# fingertip_20line_2.net
KiCad netlist of a schematic drawn in EAGLE
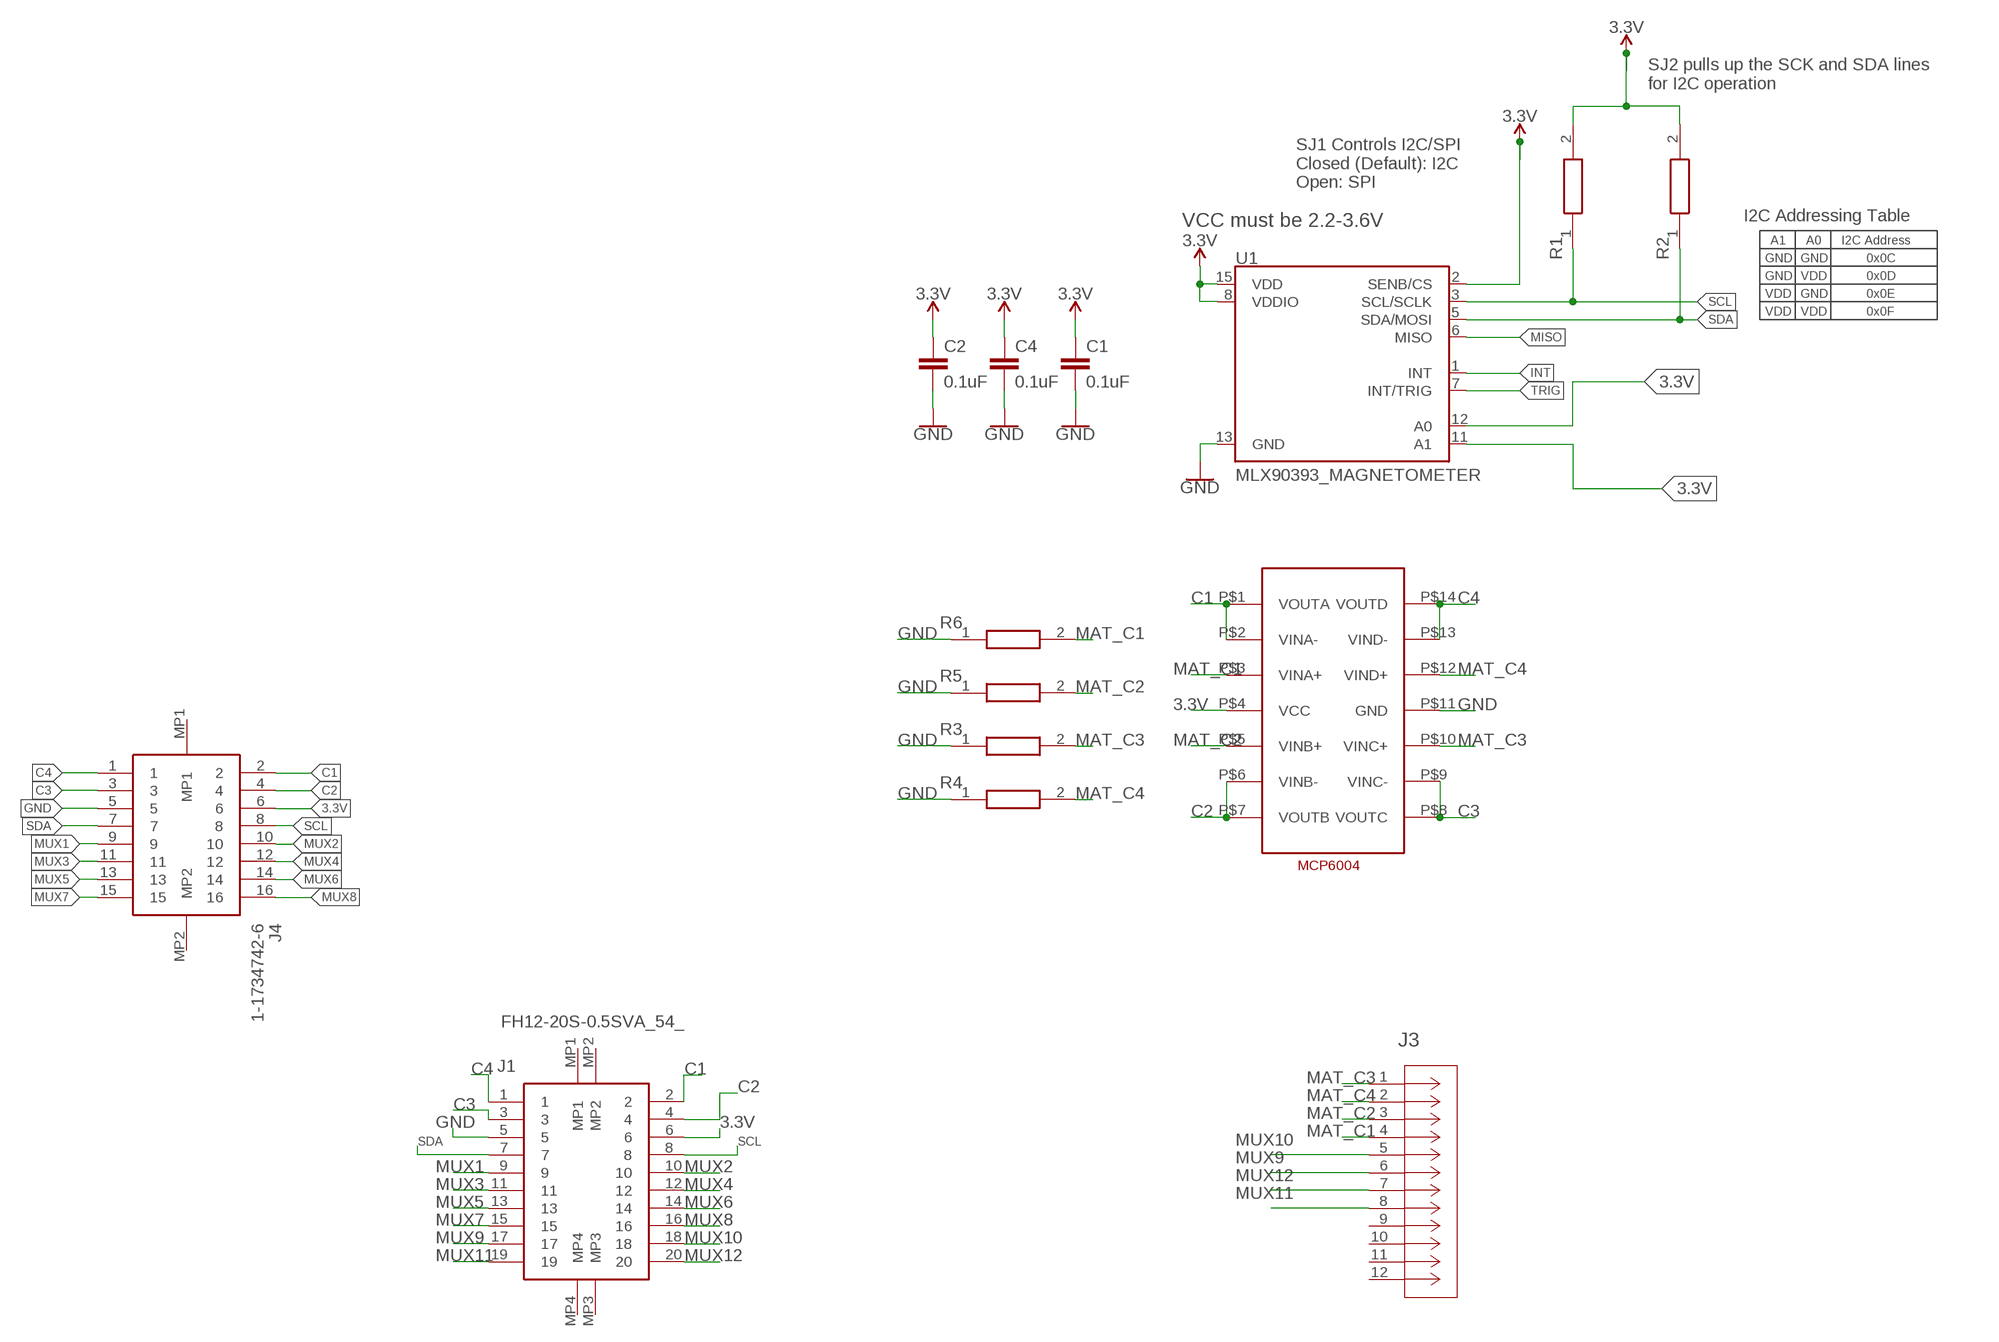
[diagram p0: schematic, sheet 1]

(export (version "E")
  (design (tool "Eeschema 10.0.6"))
  (components
    (comp (ref "C1")
      (value "0.1uF")
      (footprint "eagle-import:0603")
      (libsource (lib "eagle-import") (part "0.1UF-0603-25V-(+80/-20%)"))
    )
    (comp (ref "C2")
      (value "0.1uF")
      (footprint "eagle-import:0603")
      (libsource (lib "eagle-import") (part "0.1UF-0603-25V-(+80/-20%)"))
    )
    (comp (ref "C4")
      (value "0.1uF")
      (footprint "eagle-import:0603")
      (libsource (lib "eagle-import") (part "0.1UF-0603-25V-(+80/-20%)"))
    )
    (comp (ref "J1")
      (value "FH12-20S-0.5SVA_54_")
      (footprint "eagle-import:FH1220S05SVA54")
      (fields
        (field (name "MANUFACTURER_PART_NUMBER") "FH12-20S-0.5SVA(54)")
        (field (name "RS_PART_NUMBER") "1760102P")
      )
      (libsource (lib "eagle-import") (part "FH12-20S-0.5SVA_54_"))
    )
    (comp (ref "J3")
      (value "FH12-8S-1SV(55)")
      (footprint "eagle-import:CON8_1X8_DUTB1_HRS_HIR")
      (fields (field (name "COPYRIGHT") "Copyright (C) 2018 Accelerated Designs. All rights reserved"))
      (libsource (lib "eagle-import") (part "FH12-8S-1SV(55)"))
    )
    (comp (ref "J4")
      (value "1-1734742-6")
      (footprint "eagle-import:117347426")
      (fields (field (name "MOUSER_PART_NUMBER") "571-1-1734742-6"))
      (libsource (lib "eagle-import") (part "1-1734742-6"))
    )
    (comp (ref "R1")
      (value "ERJ-S02J103X")
      (footprint "eagle-import:RESC1005X40N")
      (libsource (lib "eagle-import") (part "ERJ-S02J103X"))
    )
    (comp (ref "R2")
      (value "ERJ-S02J103X")
      (footprint "eagle-import:RESC1005X40N")
      (libsource (lib "eagle-import") (part "ERJ-S02J103X"))
    )
    (comp (ref "R3")
      (value "ERJ-S02J103X")
      (footprint "eagle-import:RESC1005X40N")
      (libsource (lib "eagle-import") (part "ERJ-S02J103X"))
    )
    (comp (ref "R4")
      (value "ERJ-S02J103X")
      (footprint "eagle-import:RESC1005X40N")
      (libsource (lib "eagle-import") (part "ERJ-S02J103X"))
    )
    (comp (ref "R5")
      (value "ERJ-S02J103X")
      (footprint "eagle-import:RESC1005X40N")
      (libsource (lib "eagle-import") (part "ERJ-S02J103X"))
    )
    (comp (ref "R6")
      (value "ERJ-S02J103X")
      (footprint "eagle-import:RESC1005X40N")
      (libsource (lib "eagle-import") (part "ERJ-S02J103X"))
    )
    (comp (ref "U$2")
      (value "DECADE-MCP6004")
      (footprint "eagle-import:DECADE-MCP6003")
      (libsource (lib "eagle-import") (part "DECADE-MCP6004"))
    )
    (comp (ref "U1")
      (value "MLX90393_MAGNETOMETER")
      (footprint "eagle-import:QFN-16_WITH_AXIES")
      (libsource (lib "eagle-import") (part "MLX90393_MAGNETOMETER"))
    )
  )
  (nets
    (net (code "1") (name "/MAT_C1") (class "Default")
      (node (ref "J3") (pin "4") (pinfunction "4_4") (pintype "passive"))
      (node (ref "R6") (pin "2") (pinfunction "2_2") (pintype "bidirectional"))
      (node (ref "U$2") (pin "P$3") (pinfunction "VINA+_P$3") (pintype "bidirectional"))
    )
    (net (code "2") (name "/MAT_C2") (class "Default")
      (node (ref "J3") (pin "3") (pinfunction "3_3") (pintype "passive"))
      (node (ref "R5") (pin "2") (pinfunction "2_2") (pintype "bidirectional"))
      (node (ref "U$2") (pin "P$5") (pinfunction "VINB+_P$5") (pintype "bidirectional"))
    )
    (net (code "3") (name "/MAT_C3") (class "Default")
      (node (ref "J3") (pin "1") (pinfunction "1_1") (pintype "passive"))
      (node (ref "R3") (pin "2") (pinfunction "2_2") (pintype "bidirectional"))
      (node (ref "U$2") (pin "P$10") (pinfunction "VINC+_P$10") (pintype "bidirectional"))
    )
    (net (code "4") (name "/MAT_C4") (class "Default")
      (node (ref "J3") (pin "2") (pinfunction "2_2") (pintype "passive"))
      (node (ref "R4") (pin "2") (pinfunction "2_2") (pintype "bidirectional"))
      (node (ref "U$2") (pin "P$12") (pinfunction "VIND+_P$12") (pintype "bidirectional"))
    )
    (net (code "5") (name "/MUX9") (class "Default")
      (node (ref "J1") (pin "17") (pinfunction "17_17") (pintype "bidirectional"))
      (node (ref "J3") (pin "6") (pinfunction "6_6") (pintype "passive"))
    )
    (net (code "6") (name "/MUX10") (class "Default")
      (node (ref "J1") (pin "18") (pinfunction "18_18") (pintype "bidirectional"))
      (node (ref "J3") (pin "5") (pinfunction "5_5") (pintype "passive"))
    )
    (net (code "7") (name "/MUX11") (class "Default")
      (node (ref "J1") (pin "19") (pinfunction "19_19") (pintype "bidirectional"))
      (node (ref "J3") (pin "8") (pinfunction "8_8") (pintype "passive"))
    )
    (net (code "8") (name "/MUX12") (class "Default")
      (node (ref "J1") (pin "20") (pinfunction "20_20") (pintype "bidirectional"))
      (node (ref "J3") (pin "7") (pinfunction "7_7") (pintype "passive"))
    )
    (net (code "9") (name "3.3V") (class "Default")
      (node (ref "C1") (pin "1") (pinfunction "1_1") (pintype "passive"))
      (node (ref "C2") (pin "1") (pinfunction "1_1") (pintype "passive"))
      (node (ref "C4") (pin "1") (pinfunction "1_1") (pintype "passive"))
      (node (ref "J1") (pin "6") (pinfunction "6_6") (pintype "bidirectional"))
      (node (ref "J4") (pin "6") (pinfunction "6_6") (pintype "bidirectional"))
      (node (ref "R1") (pin "2") (pinfunction "2_2") (pintype "bidirectional"))
      (node (ref "R2") (pin "2") (pinfunction "2_2") (pintype "bidirectional"))
      (node (ref "U$2") (pin "P$4") (pinfunction "VCC_P$4") (pintype "bidirectional"))
      (node (ref "U1") (pin "11") (pinfunction "A1_11") (pintype "bidirectional"))
      (node (ref "U1") (pin "12") (pinfunction "A0_12") (pintype "bidirectional"))
      (node (ref "U1") (pin "15") (pinfunction "VDD_15") (pintype "bidirectional"))
      (node (ref "U1") (pin "2") (pinfunction "SENB/CS_2") (pintype "bidirectional"))
      (node (ref "U1") (pin "8") (pinfunction "VDDIO_8") (pintype "bidirectional"))
    )
    (net (code "10") (name "C1") (class "Default")
      (node (ref "J1") (pin "2") (pinfunction "2_2") (pintype "bidirectional"))
      (node (ref "J4") (pin "2") (pinfunction "2_2") (pintype "bidirectional"))
      (node (ref "U$2") (pin "P$1") (pinfunction "VOUTA_P$1") (pintype "bidirectional"))
      (node (ref "U$2") (pin "P$2") (pinfunction "VINA-_P$2") (pintype "bidirectional"))
    )
    (net (code "11") (name "C2") (class "Default")
      (node (ref "J1") (pin "4") (pinfunction "4_4") (pintype "bidirectional"))
      (node (ref "J4") (pin "4") (pinfunction "4_4") (pintype "bidirectional"))
      (node (ref "U$2") (pin "P$6") (pinfunction "VINB-_P$6") (pintype "bidirectional"))
      (node (ref "U$2") (pin "P$7") (pinfunction "VOUTB_P$7") (pintype "bidirectional"))
    )
    (net (code "12") (name "C3") (class "Default")
      (node (ref "J1") (pin "3") (pinfunction "3_3") (pintype "bidirectional"))
      (node (ref "J4") (pin "3") (pinfunction "3_3") (pintype "bidirectional"))
      (node (ref "U$2") (pin "P$8") (pinfunction "VOUTC_P$8") (pintype "bidirectional"))
      (node (ref "U$2") (pin "P$9") (pinfunction "VINC-_P$9") (pintype "bidirectional"))
    )
    (net (code "13") (name "C4") (class "Default")
      (node (ref "J1") (pin "1") (pinfunction "1_1") (pintype "bidirectional"))
      (node (ref "J4") (pin "1") (pinfunction "1_1") (pintype "bidirectional"))
      (node (ref "U$2") (pin "P$13") (pinfunction "VIND-_P$13") (pintype "bidirectional"))
      (node (ref "U$2") (pin "P$14") (pinfunction "VOUTD_P$14") (pintype "bidirectional"))
    )
    (net (code "14") (name "GND") (class "Default")
      (node (ref "C1") (pin "2") (pinfunction "2_2") (pintype "passive"))
      (node (ref "C2") (pin "2") (pinfunction "2_2") (pintype "passive"))
      (node (ref "C4") (pin "2") (pinfunction "2_2") (pintype "passive"))
      (node (ref "J1") (pin "5") (pinfunction "5_5") (pintype "bidirectional"))
      (node (ref "J4") (pin "5") (pinfunction "5_5") (pintype "bidirectional"))
      (node (ref "R3") (pin "1") (pinfunction "1_1") (pintype "bidirectional"))
      (node (ref "R4") (pin "1") (pinfunction "1_1") (pintype "bidirectional"))
      (node (ref "R5") (pin "1") (pinfunction "1_1") (pintype "bidirectional"))
      (node (ref "R6") (pin "1") (pinfunction "1_1") (pintype "bidirectional"))
      (node (ref "U$2") (pin "P$11") (pinfunction "GND_P$11") (pintype "bidirectional"))
      (node (ref "U1") (pin "13") (pinfunction "GND_13") (pintype "bidirectional"))
    )
    (net (code "15") (name "INT") (class "Default")
      (node (ref "U1") (pin "1") (pinfunction "INT_1") (pintype "bidirectional"))
    )
    (net (code "16") (name "MISO") (class "Default")
      (node (ref "U1") (pin "6") (pinfunction "MISO_6") (pintype "bidirectional"))
    )
    (net (code "17") (name "MUX1") (class "Default")
      (node (ref "J1") (pin "9") (pinfunction "9_9") (pintype "bidirectional"))
      (node (ref "J4") (pin "9") (pinfunction "9_9") (pintype "bidirectional"))
    )
    (net (code "18") (name "MUX2") (class "Default")
      (node (ref "J1") (pin "10") (pinfunction "10_10") (pintype "bidirectional"))
      (node (ref "J4") (pin "10") (pinfunction "10_10") (pintype "bidirectional"))
    )
    (net (code "19") (name "MUX3") (class "Default")
      (node (ref "J1") (pin "11") (pinfunction "11_11") (pintype "bidirectional"))
      (node (ref "J4") (pin "11") (pinfunction "11_11") (pintype "bidirectional"))
    )
    (net (code "20") (name "MUX4") (class "Default")
      (node (ref "J1") (pin "12") (pinfunction "12_12") (pintype "bidirectional"))
      (node (ref "J4") (pin "12") (pinfunction "12_12") (pintype "bidirectional"))
    )
    (net (code "21") (name "MUX5") (class "Default")
      (node (ref "J1") (pin "13") (pinfunction "13_13") (pintype "bidirectional"))
      (node (ref "J4") (pin "13") (pinfunction "13_13") (pintype "bidirectional"))
    )
    (net (code "22") (name "MUX6") (class "Default")
      (node (ref "J1") (pin "14") (pinfunction "14_14") (pintype "bidirectional"))
      (node (ref "J4") (pin "14") (pinfunction "14_14") (pintype "bidirectional"))
    )
    (net (code "23") (name "MUX7") (class "Default")
      (node (ref "J1") (pin "15") (pinfunction "15_15") (pintype "bidirectional"))
      (node (ref "J4") (pin "15") (pinfunction "15_15") (pintype "bidirectional"))
    )
    (net (code "24") (name "MUX8") (class "Default")
      (node (ref "J1") (pin "16") (pinfunction "16_16") (pintype "bidirectional"))
      (node (ref "J4") (pin "16") (pinfunction "16_16") (pintype "bidirectional"))
    )
    (net (code "25") (name "SCL") (class "Default")
      (node (ref "J1") (pin "8") (pinfunction "8_8") (pintype "bidirectional"))
      (node (ref "J4") (pin "8") (pinfunction "8_8") (pintype "bidirectional"))
      (node (ref "R1") (pin "1") (pinfunction "1_1") (pintype "bidirectional"))
      (node (ref "U1") (pin "3") (pinfunction "SCL/SCLK_3") (pintype "bidirectional"))
    )
    (net (code "26") (name "SDA") (class "Default")
      (node (ref "J1") (pin "7") (pinfunction "7_7") (pintype "bidirectional"))
      (node (ref "J4") (pin "7") (pinfunction "7_7") (pintype "bidirectional"))
      (node (ref "R2") (pin "1") (pinfunction "1_1") (pintype "bidirectional"))
      (node (ref "U1") (pin "5") (pinfunction "SDA/MOSI_5") (pintype "bidirectional"))
    )
    (net (code "27") (name "TRIG") (class "Default")
      (node (ref "U1") (pin "7") (pinfunction "INT/TRIG_7") (pintype "bidirectional"))
    )
    (net (code "28") (name "unconnected-(J1-PadMP1)") (class "Default")
      (node (ref "J1") (pin "MP1") (pinfunction "MP1_MP1") (pintype "bidirectional"))
    )
    (net (code "29") (name "unconnected-(J1-PadMP2)") (class "Default")
      (node (ref "J1") (pin "MP2") (pinfunction "MP2_MP2") (pintype "bidirectional"))
    )
    (net (code "30") (name "unconnected-(J1-PadMP3)") (class "Default")
      (node (ref "J1") (pin "MP3") (pinfunction "MP3_MP3") (pintype "bidirectional"))
    )
    (net (code "31") (name "unconnected-(J1-PadMP4)") (class "Default")
      (node (ref "J1") (pin "MP4") (pinfunction "MP4_MP4") (pintype "bidirectional"))
    )
    (net (code "32") (name "unconnected-(J3-Pad9)") (class "Default")
      (node (ref "J3") (pin "9") (pinfunction "9_9") (pintype "passive"))
    )
    (net (code "33") (name "unconnected-(J3-Pad10)") (class "Default")
      (node (ref "J3") (pin "10") (pinfunction "10_10") (pintype "passive"))
    )
    (net (code "34") (name "unconnected-(J3-Pad11)") (class "Default")
      (node (ref "J3") (pin "11") (pinfunction "11_11") (pintype "passive"))
    )
    (net (code "35") (name "unconnected-(J3-Pad12)") (class "Default")
      (node (ref "J3") (pin "12") (pinfunction "12_12") (pintype "passive"))
    )
    (net (code "36") (name "unconnected-(J4-PadMP1)") (class "Default")
      (node (ref "J4") (pin "MP1") (pinfunction "MP1_MP1") (pintype "bidirectional"))
    )
    (net (code "37") (name "unconnected-(J4-PadMP2)") (class "Default")
      (node (ref "J4") (pin "MP2") (pinfunction "MP2_MP2") (pintype "bidirectional"))
    )
  )
)
